# lnk304.net
KiCad netlist of a schematic drawn in EAGLE
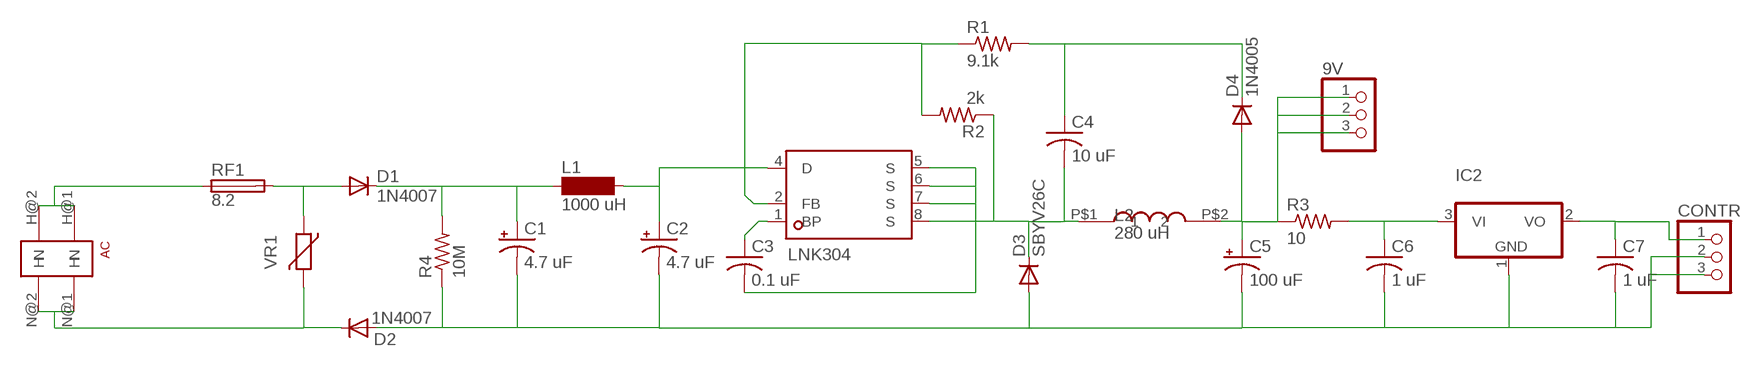
[diagram p0: schematic, sheet 1]

(export (version "E")
  (design (tool "Eeschema 10.0.6"))
  (components
    (comp (ref "9V")
      (value "PINHD-1X3")
      (footprint "eagle-import:1X03")
      (libsource (lib "eagle-import") (part "PINHD-1X3"))
    )
    (comp (ref "AC")
      (value "TBLOCK02X2")
      (footprint "eagle-import:TBLOCK02X2")
      (libsource (lib "eagle-import") (part "TBLOCK02X2"))
    )
    (comp (ref "C1")
      (value "4.7 uF")
      (footprint "eagle-import:E5-10,5")
      (libsource (lib "eagle-import") (part "CPOL-USE5-10.5"))
    )
    (comp (ref "C2")
      (value "4.7 uF")
      (footprint "eagle-import:E5-10,5")
      (libsource (lib "eagle-import") (part "CPOL-USE5-10.5"))
    )
    (comp (ref "C3")
      (value "0.1 uF")
      (footprint "eagle-import:C0603")
      (libsource (lib "eagle-import") (part "C-USC0603"))
    )
    (comp (ref "C4")
      (value "10 uF")
      (footprint "eagle-import:C0603")
      (libsource (lib "eagle-import") (part "C-USC0603"))
    )
    (comp (ref "C5")
      (value "100 uF")
      (footprint "eagle-import:E2-4")
      (libsource (lib "eagle-import") (part "CPOL-USE2-4"))
    )
    (comp (ref "C6")
      (value "1 uF")
      (footprint "eagle-import:C0603")
      (libsource (lib "eagle-import") (part "C-USC0603"))
    )
    (comp (ref "C7")
      (value "1 uF")
      (footprint "eagle-import:C0603")
      (libsource (lib "eagle-import") (part "C-USC0603"))
    )
    (comp (ref "CONTR")
      (value "PINHD-1X3")
      (footprint "eagle-import:1X03")
      (libsource (lib "eagle-import") (part "PINHD-1X3"))
    )
    (comp (ref "D1")
      (value "1N4007")
      (footprint "eagle-import:DO41-10")
      (libsource (lib "eagle-import") (part "1N4004"))
    )
    (comp (ref "D2")
      (value "1N4007")
      (footprint "eagle-import:DO41-10")
      (libsource (lib "eagle-import") (part "1N4004"))
    )
    (comp (ref "D3")
      (value "SBYV26C")
      (footprint "eagle-import:DO41-10")
      (libsource (lib "eagle-import") (part "1N4004"))
    )
    (comp (ref "D4")
      (value "1N4005")
      (footprint "eagle-import:DO41-10")
      (libsource (lib "eagle-import") (part "1N4004"))
    )
    (comp (ref "IC2")
      (value "MCP1703CB")
      (footprint "eagle-import:SOT23")
      (libsource (lib "eagle-import") (part "MCP1703CB"))
    )
    (comp (ref "L1")
      (value "1000 uH")
      (footprint "eagle-import:BS11")
      (libsource (lib "eagle-import") (part "BS11"))
    )
    (comp (ref "L2")
      (value "280 uH")
      (footprint "eagle-import:ELL-6UH681M")
      (libsource (lib "eagle-import") (part "ELL-6UH681M"))
    )
    (comp (ref "LNK304")
      (value "LNK30X")
      (footprint "eagle-import:SO08C")
      (libsource (lib "eagle-import") (part "LNK30X"))
    )
    (comp (ref "R1")
      (value "9.1k")
      (footprint "eagle-import:R0603")
      (libsource (lib "eagle-import") (part "R-US_R0603"))
    )
    (comp (ref "R2")
      (value "2k")
      (footprint "eagle-import:R0603")
      (libsource (lib "eagle-import") (part "R-US_R0603"))
    )
    (comp (ref "R3")
      (value "10")
      (footprint "eagle-import:R1206")
      (libsource (lib "eagle-import") (part "R-US_R1206"))
    )
    (comp (ref "R4")
      (value "10M")
      (footprint "eagle-import:R1206")
      (libsource (lib "eagle-import") (part "resistor_R-US_R1206"))
    )
    (comp (ref "RF1")
      (value "8.2")
      (footprint "eagle-import:PICOFUSE")
      (libsource (lib "eagle-import") (part "FUSEPICOFUSE"))
    )
    (comp (ref "VR1")
      (value "VARISTOR-7,5")
      (footprint "eagle-import:R-7,5")
      (libsource (lib "eagle-import") (part "VARISTOR-7,5"))
    )
  )
  (nets
    (net (code "1") (name "Net-(AC-H-PadH@1)") (class "Default")
      (node (ref "AC") (pin "H@1") (pinfunction "H_H@1") (pintype "bidirectional"))
      (node (ref "AC") (pin "H@2") (pinfunction "H_H@2") (pintype "bidirectional"))
      (node (ref "RF1") (pin "1") (pinfunction "1_1") (pintype "passive"))
    )
    (net (code "2") (name "Net-(AC-N-PadN@1)") (class "Default")
      (node (ref "AC") (pin "N@1") (pinfunction "N_N@1") (pintype "bidirectional"))
      (node (ref "AC") (pin "N@2") (pinfunction "N_N@2") (pintype "bidirectional"))
      (node (ref "D2") (pin "C") (pinfunction "C_C") (pintype "passive"))
      (node (ref "VR1") (pin "2") (pinfunction "2_2") (pintype "passive"))
    )
    (net (code "3") (name "Net-(C1-Pad+)") (class "Default")
      (node (ref "C1") (pin "+") (pinfunction "+_+") (pintype "passive"))
      (node (ref "D1") (pin "C") (pinfunction "C_C") (pintype "passive"))
      (node (ref "L1") (pin "1") (pinfunction "1_1") (pintype "passive"))
      (node (ref "R4") (pin "2") (pinfunction "2_2") (pintype "passive"))
    )
    (net (code "4") (name "Net-(C4-Pad1)") (class "Default")
      (node (ref "C4") (pin "1") (pinfunction "1_1") (pintype "passive"))
      (node (ref "D4") (pin "C") (pinfunction "C_C") (pintype "passive"))
      (node (ref "R1") (pin "2") (pinfunction "2_2") (pintype "passive"))
    )
    (net (code "5") (name "Net-(D1-PadA)") (class "Default")
      (node (ref "D1") (pin "A") (pinfunction "A_A") (pintype "passive"))
      (node (ref "RF1") (pin "2") (pinfunction "2_2") (pintype "passive"))
      (node (ref "VR1") (pin "1") (pinfunction "1_1") (pintype "passive"))
    )
    (net (code "6") (name "Net-(IC2-GND)") (class "Default")
      (node (ref "C1") (pin "-") (pinfunction "-_-") (pintype "passive"))
      (node (ref "C2") (pin "-") (pinfunction "-_-") (pintype "passive"))
      (node (ref "C5") (pin "-") (pinfunction "-_-") (pintype "passive"))
      (node (ref "C6") (pin "2") (pinfunction "2_2") (pintype "passive"))
      (node (ref "C7") (pin "2") (pinfunction "2_2") (pintype "passive"))
      (node (ref "CONTR") (pin "2") (pinfunction "2_2") (pintype "passive"))
      (node (ref "CONTR") (pin "3") (pinfunction "3_3") (pintype "passive"))
      (node (ref "D2") (pin "A") (pinfunction "A_A") (pintype "passive"))
      (node (ref "D3") (pin "A") (pinfunction "A_A") (pintype "passive"))
      (node (ref "IC2") (pin "1") (pinfunction "GND_1") (pintype "passive"))
      (node (ref "R4") (pin "1") (pinfunction "1_1") (pintype "passive"))
    )
    (net (code "7") (name "Net-(IC2-VI)") (class "Default")
      (node (ref "C6") (pin "1") (pinfunction "1_1") (pintype "passive"))
      (node (ref "IC2") (pin "3") (pinfunction "VI_3") (pintype "input"))
      (node (ref "R3") (pin "2") (pinfunction "2_2") (pintype "passive"))
    )
    (net (code "8") (name "Net-(IC2-VO)") (class "Default")
      (node (ref "C7") (pin "1") (pinfunction "1_1") (pintype "passive"))
      (node (ref "CONTR") (pin "1") (pinfunction "1_1") (pintype "passive"))
      (node (ref "IC2") (pin "2") (pinfunction "VO_2") (pintype "passive"))
    )
    (net (code "9") (name "Net-(L2-1)") (class "Default")
      (node (ref "C3") (pin "2") (pinfunction "2_2") (pintype "passive"))
      (node (ref "C4") (pin "2") (pinfunction "2_2") (pintype "passive"))
      (node (ref "D3") (pin "C") (pinfunction "C_C") (pintype "passive"))
      (node (ref "L2") (pin "P$1") (pinfunction "1_P$1") (pintype "bidirectional"))
      (node (ref "LNK304") (pin "5") (pinfunction "S_5") (pintype "output"))
      (node (ref "LNK304") (pin "6") (pinfunction "S_6") (pintype "output"))
      (node (ref "LNK304") (pin "7") (pinfunction "S_7") (pintype "output"))
      (node (ref "LNK304") (pin "8") (pinfunction "S_8") (pintype "output"))
      (node (ref "R2") (pin "1") (pinfunction "1_1") (pintype "passive"))
    )
    (net (code "10") (name "Net-(L2-2)") (class "Default")
      (node (ref "9V") (pin "1") (pinfunction "1_1") (pintype "passive"))
      (node (ref "9V") (pin "2") (pinfunction "2_2") (pintype "passive"))
      (node (ref "9V") (pin "3") (pinfunction "3_3") (pintype "passive"))
      (node (ref "C5") (pin "+") (pinfunction "+_+") (pintype "passive"))
      (node (ref "D4") (pin "A") (pinfunction "A_A") (pintype "passive"))
      (node (ref "L2") (pin "P$2") (pinfunction "2_P$2") (pintype "bidirectional"))
      (node (ref "R3") (pin "1") (pinfunction "1_1") (pintype "passive"))
    )
    (net (code "11") (name "Net-(LNK304-BP)") (class "Default")
      (node (ref "C3") (pin "1") (pinfunction "1_1") (pintype "passive"))
      (node (ref "LNK304") (pin "1") (pinfunction "BP_1") (pintype "output"))
    )
    (net (code "12") (name "Net-(LNK304-D)") (class "Default")
      (node (ref "C2") (pin "+") (pinfunction "+_+") (pintype "passive"))
      (node (ref "L1") (pin "2") (pinfunction "2_2") (pintype "passive"))
      (node (ref "LNK304") (pin "4") (pinfunction "D_4") (pintype "input"))
    )
    (net (code "13") (name "Net-(LNK304-FB)") (class "Default")
      (node (ref "LNK304") (pin "2") (pinfunction "FB_2") (pintype "input"))
      (node (ref "R1") (pin "1") (pinfunction "1_1") (pintype "passive"))
      (node (ref "R2") (pin "2") (pinfunction "2_2") (pintype "passive"))
    )
  )
)
